# amp-27dBm.net
KiCad netlist of a schematic drawn in Altium Designer
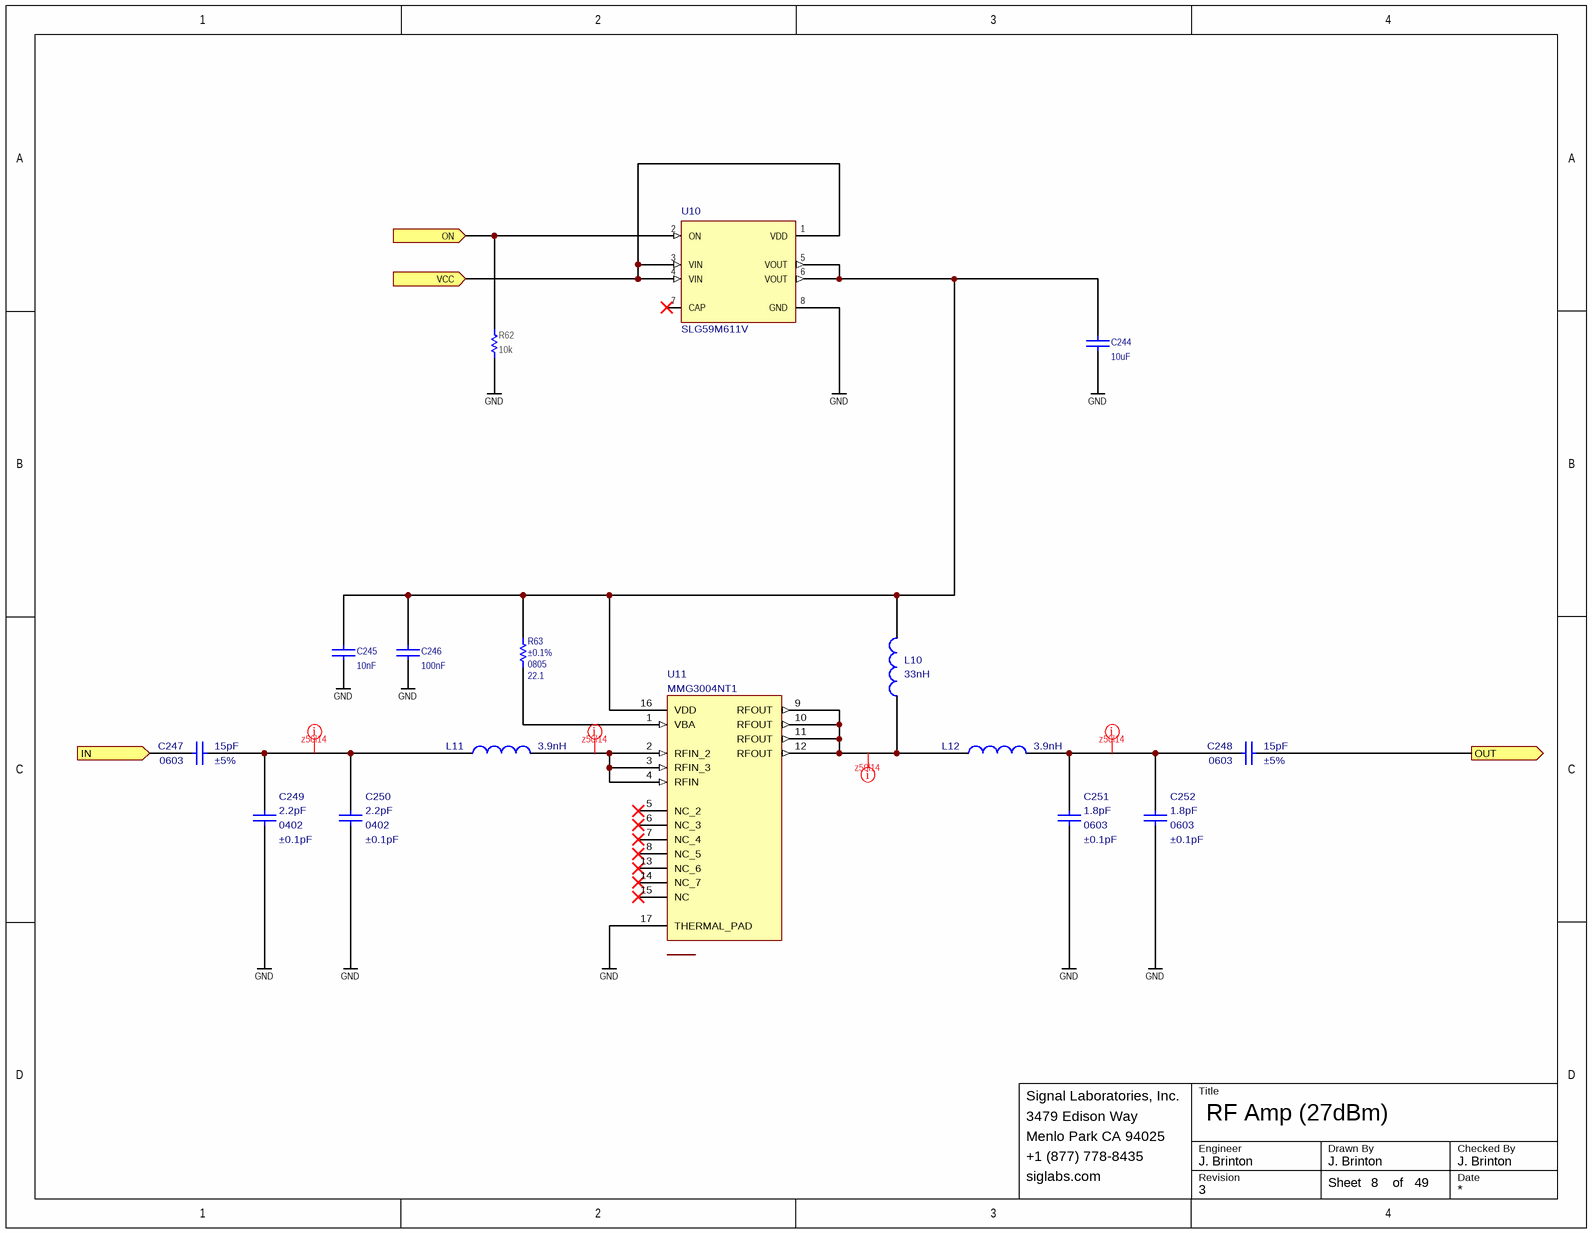
[diagram p0: amp-27dBm.SchDoc]

(export (version "E")
  (design (tool "Eeschema 10.0.6"))
  (components
    (comp (ref "C244")
      (value "10uF")
      (footprint "CAPC160X80X90L20N")
      (description "Ceramic Capacitor 10uF ±20% 25V X5R 0603")
      (fields (field (name "MANUFACTURER") "Murata") (field (name "VOLTAGE") "25V"))
      (libsource (lib "generic") (part "CAP 0603"))
    )
    (comp (ref "C245")
      (value "10nF")
      (footprint "CAPC100X50X55L25N")
      (description "Ceramic Capacitor 10nF ±10% 50V X7R 0402")
      (fields (field (name "VOLTAGE") "50V") (field (name "MANUFACTURER") "Murata"))
      (libsource (lib "Graviton") (part "CAP 0402"))
    )
    (comp (ref "C246")
      (value "100nF")
      (footprint "CAPC100X50X55L25N")
      (description "Ceramic Capacitor 100nF ±10% 16V X7R 0402")
      (fields (field (name "VOLTAGE") "16V") (field (name "MANUFACTURER") "Murata"))
      (libsource (lib "Graviton") (part "CAP 0402"))
    )
    (comp (ref "C247")
      (value "15pF")
      (footprint "CAPC160X80X90L20N")
      (description "Ceramic Capacitor 15pF ±5% NP0 0603")
      (fields
        (field (name "MANUFACTURER") "Murata")
        (field (name "TOLERANCE") "±5%")
        (field (name "VOLTAGE") "50V")
        (field (name "PACKAGE") "0603")
      )
      (libsource (lib "generic") (part "CAP"))
    )
    (comp (ref "C248")
      (value "15pF")
      (footprint "CAPC160X80X90L20N")
      (description "Ceramic Capacitor 15pF ±5% NP0 0603")
      (fields
        (field (name "MANUFACTURER") "Murata")
        (field (name "TOLERANCE") "±5%")
        (field (name "VOLTAGE") "50V")
        (field (name "PACKAGE") "0603")
      )
      (libsource (lib "generic") (part "CAP"))
    )
    (comp (ref "C249")
      (value "2.2pF")
      (footprint "CAPC100X50X55L25N")
      (description "Ceramic Capacitor 2.2pF ±0.1pF 50V C0G 0402")
      (fields
        (field (name "MANUFACTURER") "Vishay")
        (field (name "TOLERANCE") "±0.1pF")
        (field (name "VOLTAGE") "50V")
        (field (name "PACKAGE") "0402")
      )
      (libsource (lib "generic") (part "CAP"))
    )
    (comp (ref "C250")
      (value "2.2pF")
      (footprint "CAPC100X50X55L25N")
      (description "Ceramic Capacitor 2.2pF ±0.1pF 50V C0G 0402")
      (fields
        (field (name "MANUFACTURER") "Vishay")
        (field (name "TOLERANCE") "±0.1pF")
        (field (name "VOLTAGE") "50V")
        (field (name "PACKAGE") "0402")
      )
      (libsource (lib "generic") (part "CAP"))
    )
    (comp (ref "C251")
      (value "1.8pF")
      (footprint "CAPC160X80X90L20N")
      (description "Ceramic Capacitor 1.8pF ±0.1pF NP0 0603")
      (fields
        (field (name "MANUFACTURER") "AVX")
        (field (name "TOLERANCE") "±0.1pF")
        (field (name "VOLTAGE") "200V")
        (field (name "PACKAGE") "0603")
      )
      (libsource (lib "generic") (part "CAP"))
    )
    (comp (ref "C252")
      (value "1.8pF")
      (footprint "CAPC160X80X90L20N")
      (description "Ceramic Capacitor 1.8pF ±0.1pF NP0 0603")
      (fields
        (field (name "MANUFACTURER") "AVX")
        (field (name "TOLERANCE") "±0.1pF")
        (field (name "VOLTAGE") "200V")
        (field (name "PACKAGE") "0603")
      )
      (libsource (lib "generic") (part "CAP"))
    )
    (comp (ref "L10")
      (value "33nH")
      (footprint "INDC2520X100N")
      (description "Inductor 33nH 1A")
      (fields (field (name "MANUFACTURER") "Wurth Electronics") (field (name "Comment") "744762133A"))
      (libsource (lib "generic") (part "INDUCTOR"))
    )
    (comp (ref "L11")
      (value "3.9nH")
      (footprint "0603")
      (description "Inductor 3.9nH 700mA 0603")
      (fields (field (name "MANUFACTURER") "Wurth Electronics") (field (name "Comment") "744761039C"))
      (libsource (lib "generic") (part "INDUCTOR"))
    )
    (comp (ref "L12")
      (value "3.9nH")
      (footprint "0603")
      (description "Inductor 3.9nH 700mA 0603")
      (fields (field (name "MANUFACTURER") "Wurth Electronics") (field (name "Comment") "744761039C"))
      (libsource (lib "generic") (part "INDUCTOR"))
    )
    (comp (ref "R62")
      (value "10k")
      (footprint "RESC1005X40N")
      (description "Thick Film Resistor 10k ±1% 0.1W 50V 0402")
      (fields (field (name "MANUFACTURER") "Panasonic") (field (name "TOLERANCE") "±1%"))
      (libsource (lib "generic") (part "RES"))
    )
    (comp (ref "R63")
      (value "22.1")
      (footprint "RESC2012X70N")
      (description "Thin Film Resistor 22.1 +/-0.1% SMD 0805")
      (fields
        (field (name "TOLERANCE") "±0.1%")
        (field (name "MANUFACTURER") "Vishay")
        (field (name "PACKAGE") "0805")
        (field (name "Comment") "PTN0805E22R1BST1")
      )
      (libsource (lib "generic") (part "RES"))
    )
    (comp (ref "U10")
      (value "SLG59M611V")
      (footprint "DFN200X150X80-8N")
      (description "High-Side Load Switch")
      (fields (field (name "MANUFACTURER") "Silego"))
      (libsource (lib "silego") (part "SLG59M611V"))
    )
    (comp (ref "U11")
      (value "MMG3004NT1")
      (footprint "nxp:QFN65P400X400X90-17N")
      (description "RF Amp Chip Single GP 2.4GHz 6V 16-Pin QFN EP T/R")
      (fields (field (name "MANUFACTURER") "NXP Semiconductors"))
      (libsource (lib "nxp") (part "MMG3006NT1"))
    )
  )
  (nets
    (net (code "1") (name "/IN") (class "Default")
      (node (ref "C247") (pin "1") (pinfunction "1_1") (pintype "passive"))
    )
    (net (code "2") (name "/ON") (class "Default")
      (node (ref "R62") (pin "2") (pinfunction "2_2") (pintype "passive"))
      (node (ref "U10") (pin "2") (pinfunction "ON_2") (pintype "input"))
    )
    (net (code "3") (name "/OUT") (class "Default")
      (node (ref "C248") (pin "2") (pinfunction "2_2") (pintype "passive"))
    )
    (net (code "4") (name "/VCC") (class "Default")
      (node (ref "U10") (pin "1") (pinfunction "VDD_1") (pintype "power_in"))
      (node (ref "U10") (pin "3") (pinfunction "VIN_3") (pintype "input"))
      (node (ref "U10") (pin "4") (pinfunction "VIN_4") (pintype "input"))
    )
    (net (code "5") (name "GND") (class "Default")
      (node (ref "C244") (pin "1") (pinfunction "1_1") (pintype "passive"))
      (node (ref "C245") (pin "1") (pinfunction "1_1") (pintype "passive"))
      (node (ref "C246") (pin "1") (pinfunction "1_1") (pintype "passive"))
      (node (ref "C249") (pin "1") (pinfunction "1_1") (pintype "passive"))
      (node (ref "C250") (pin "1") (pinfunction "1_1") (pintype "passive"))
      (node (ref "C251") (pin "1") (pinfunction "1_1") (pintype "passive"))
      (node (ref "C252") (pin "1") (pinfunction "1_1") (pintype "passive"))
      (node (ref "R62") (pin "1") (pinfunction "1_1") (pintype "passive"))
      (node (ref "U10") (pin "8") (pinfunction "GND_8") (pintype "power_in"))
      (node (ref "U11") (pin "17") (pinfunction "THERMAL_PAD_17") (pintype "passive"))
    )
    (net (code "6") (name "Net-(C247-Pad2)") (class "Default")
      (node (ref "C247") (pin "2") (pinfunction "2_2") (pintype "passive"))
      (node (ref "C249") (pin "2") (pinfunction "2_2") (pintype "passive"))
      (node (ref "C250") (pin "2") (pinfunction "2_2") (pintype "passive"))
      (node (ref "L11") (pin "1") (pinfunction "1_1") (pintype "passive"))
    )
    (net (code "7") (name "Net-(C248-Pad1)") (class "Default")
      (node (ref "C248") (pin "1") (pinfunction "1_1") (pintype "passive"))
      (node (ref "C251") (pin "2") (pinfunction "2_2") (pintype "passive"))
      (node (ref "C252") (pin "2") (pinfunction "2_2") (pintype "passive"))
      (node (ref "L12") (pin "2") (pinfunction "2_2") (pintype "passive"))
    )
    (net (code "8") (name "Net-(L10-Pad1)") (class "Default")
      (node (ref "L10") (pin "1") (pinfunction "1_1") (pintype "passive"))
      (node (ref "L12") (pin "1") (pinfunction "1_1") (pintype "passive"))
      (node (ref "U11") (pin "10") (pinfunction "RFOUT_10") (pintype "output"))
      (node (ref "U11") (pin "11") (pinfunction "RFOUT_11") (pintype "output"))
      (node (ref "U11") (pin "12") (pinfunction "RFOUT_12") (pintype "output"))
      (node (ref "U11") (pin "9") (pinfunction "RFOUT_9") (pintype "output"))
    )
    (net (code "9") (name "Net-(U11-RFIN)") (class "Default")
      (node (ref "L11") (pin "2") (pinfunction "2_2") (pintype "passive"))
      (node (ref "U11") (pin "2") (pinfunction "RFIN_2_2") (pintype "input"))
      (node (ref "U11") (pin "3") (pinfunction "RFIN_3_3") (pintype "input"))
      (node (ref "U11") (pin "4") (pinfunction "RFIN_4") (pintype "input"))
    )
    (net (code "10") (name "Net-(U11-VBA)") (class "Default")
      (node (ref "R63") (pin "2") (pinfunction "2_2") (pintype "passive"))
      (node (ref "U11") (pin "1") (pinfunction "VBA_1") (pintype "input"))
    )
    (net (code "11") (name "Net-(U11-VDD)") (class "Default")
      (node (ref "C244") (pin "2") (pinfunction "2_2") (pintype "passive"))
      (node (ref "C245") (pin "2") (pinfunction "2_2") (pintype "passive"))
      (node (ref "C246") (pin "2") (pinfunction "2_2") (pintype "passive"))
      (node (ref "L10") (pin "2") (pinfunction "2_2") (pintype "passive"))
      (node (ref "R63") (pin "1") (pinfunction "1_1") (pintype "passive"))
      (node (ref "U10") (pin "5") (pinfunction "VOUT_5") (pintype "output"))
      (node (ref "U10") (pin "6") (pinfunction "VOUT_6") (pintype "output"))
      (node (ref "U11") (pin "16") (pinfunction "VDD_16") (pintype "power_in"))
    )
    (net (code "12") (name "unconnected-(U10-CAP-Pad7)") (class "Default")
      (node (ref "U10") (pin "7") (pinfunction "CAP_7") (pintype "passive+no_connect"))
    )
    (net (code "13") (name "unconnected-(U11-NC-Pad15)") (class "Default")
      (node (ref "U11") (pin "15") (pinfunction "NC_15") (pintype "passive+no_connect"))
    )
    (net (code "14") (name "unconnected-(U11-NC_2-Pad5)") (class "Default")
      (node (ref "U11") (pin "5") (pinfunction "NC_2_5") (pintype "passive+no_connect"))
    )
    (net (code "15") (name "unconnected-(U11-NC_3-Pad6)") (class "Default")
      (node (ref "U11") (pin "6") (pinfunction "NC_3_6") (pintype "passive+no_connect"))
    )
    (net (code "16") (name "unconnected-(U11-NC_4-Pad7)") (class "Default")
      (node (ref "U11") (pin "7") (pinfunction "NC_4_7") (pintype "passive+no_connect"))
    )
    (net (code "17") (name "unconnected-(U11-NC_5-Pad8)") (class "Default")
      (node (ref "U11") (pin "8") (pinfunction "NC_5_8") (pintype "passive+no_connect"))
    )
    (net (code "18") (name "unconnected-(U11-NC_6-Pad13)") (class "Default")
      (node (ref "U11") (pin "13") (pinfunction "NC_6_13") (pintype "passive+no_connect"))
    )
    (net (code "19") (name "unconnected-(U11-NC_7-Pad14)") (class "Default")
      (node (ref "U11") (pin "14") (pinfunction "NC_7_14") (pintype "passive+no_connect"))
    )
  )
)
